# USB_UART.net
KiCad netlist of a schematic drawn in Altium Designer
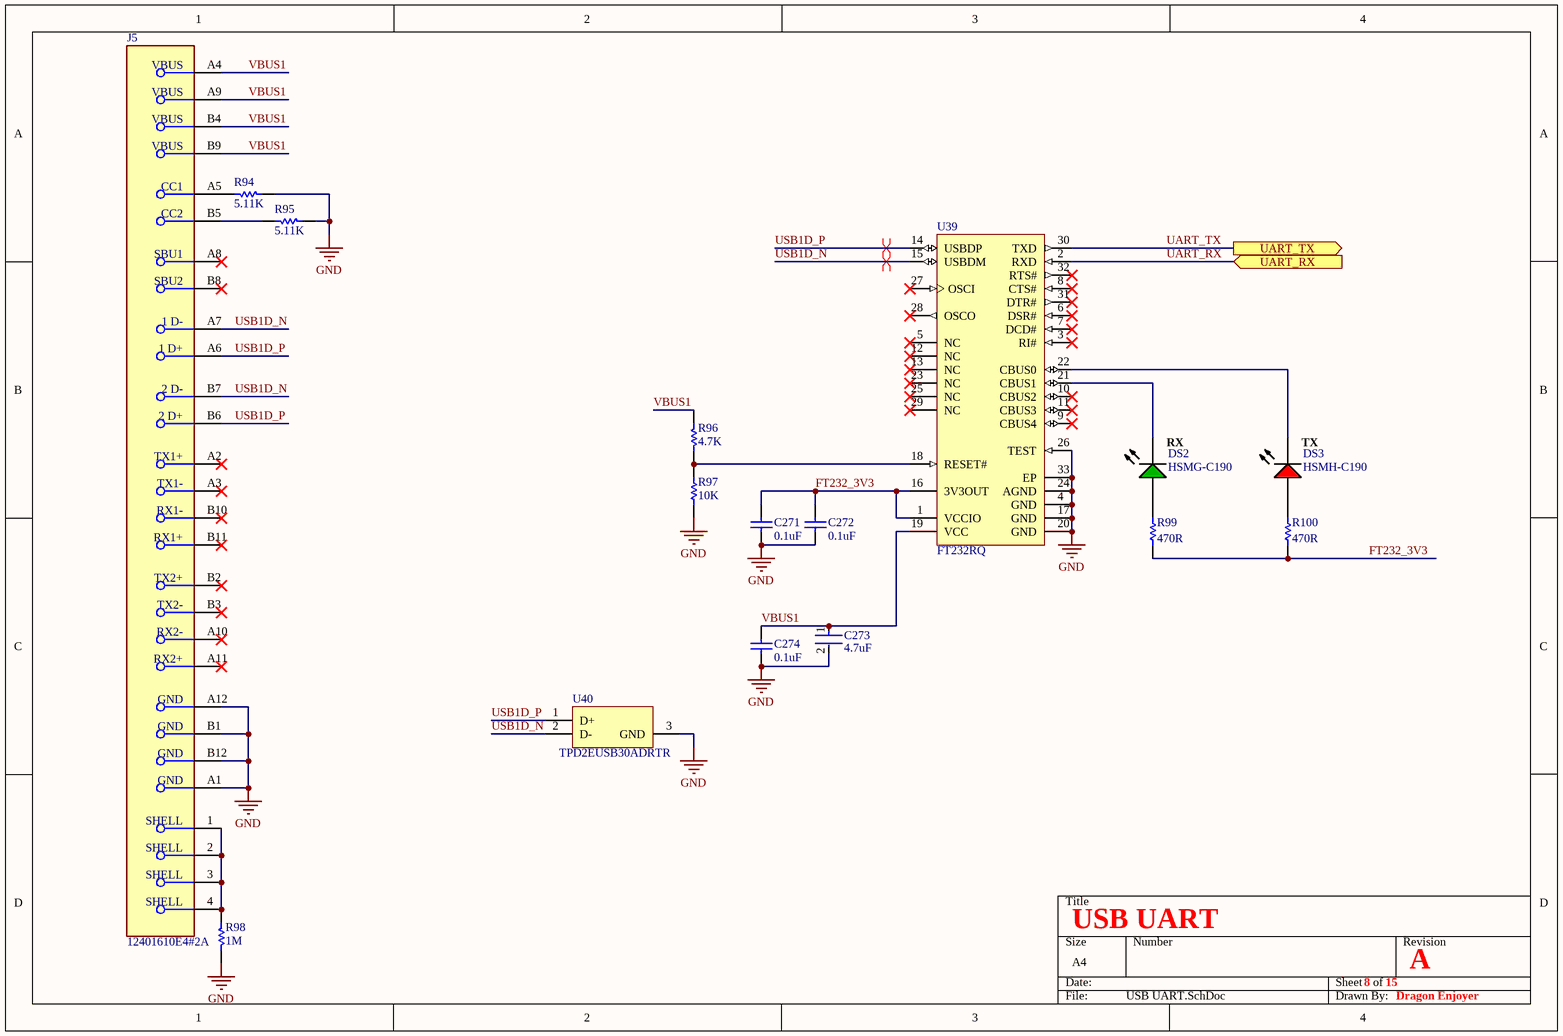
[diagram p0: USB UART.SchDoc]

(export (version "E")
  (design (tool "Eeschema 10.0.6"))
  (components
    (comp (ref "C271")
      (value "0.1uF")
      (footprint "CAPC1005X56X25LL10T15")
      (fields
        (field (name "MANUFACTURER") "AVX Interconnect / Elco")
        (field (name "PART NUMBER") "04026D104KAT2A")
      )
      (libsource (lib "Altium Content Vault") (part "CAP"))
    )
    (comp (ref "C272")
      (value "0.1uF")
      (footprint "CAPC1005X56X25LL10T15")
      (fields
        (field (name "MANUFACTURER") "AVX Interconnect / Elco")
        (field (name "PART NUMBER") "04026D104KAT2A")
      )
      (libsource (lib "Altium Content Vault") (part "CAP"))
    )
    (comp (ref "C273")
      (value "C1005X5R1A475K050BC")
      (footprint "FP-C1005-050-0_15-MFG")
      (description "CAP CER 4.7UF 10V X5R 0402")
      (fields (field (name "TOLERANCE") "10%") (field (name "CAPACITANCE") "4.7uF"))
      (libsource (lib "Altium Content Vault") (part "b4654b650e69147ec39a6b967a45e02"))
    )
    (comp (ref "C274")
      (value "0.1uF")
      (footprint "CAPC1005X56X25LL10T15")
      (fields
        (field (name "MANUFACTURER") "AVX Interconnect / Elco")
        (field (name "PART NUMBER") "04026D104KAT2A")
      )
      (libsource (lib "Altium Content Vault") (part "CAP"))
    )
    (comp (ref "DS2")
      (value "HSMG-C190")
      (footprint "AVAG-HSMX-C190_V")
      (description "Chip LED, Green, 2.2 V, -40 to 85 degC, 2-Pin SMD, RoHS, Tape and Reel")
      (libsource (lib "Altium Content Vault") (part "LED-GREEN-AK-2"))
    )
    (comp (ref "DS3")
      (value "HSMH-C190")
      (footprint "AVAG-HSMX-C190_V")
      (description "LED Uni-Color Red, 65 mW, 20 mA, -40 to 85 degC, 2-Pin SMD, RoHS, Tape and Reel")
      (libsource (lib "Altium Content Vault") (part "LED-RED-AK-2"))
    )
    (comp (ref "J5")
      (value "12401610E4#2A")
      (footprint "FP-12401610E4#2A-MFG")
      (description "CONN RCP USB3.1 TYPEC 24P SMD RA")
      (libsource (lib "Altium Content Vault") (part "7c76f4c47d7e2af8b8797da79635f2a"))
    )
    (comp (ref "R94")
      (value "5.11K")
      (footprint "RESC0603X28X15ML05T05")
      (fields (field (name "PART NUMBER") "CRCW02015K11FNED") (field (name "MANUFACTURER") "Vishay Dale"))
      (libsource (lib "Altium Content Vault") (part "RES"))
    )
    (comp (ref "R95")
      (value "5.11K")
      (footprint "RESC0603X28X15ML05T05")
      (fields (field (name "PART NUMBER") "CRCW02015K11FNED") (field (name "MANUFACTURER") "Vishay Dale"))
      (libsource (lib "Altium Content Vault") (part "RES"))
    )
    (comp (ref "R96")
      (value "4.7K")
      (footprint "RESC1005X40X25LL05T10")
      (fields (field (name "PART NUMBER") "RC0402JR-074K7L") (field (name "MANUFACTURER") "Yageo / Phycomp"))
      (libsource (lib "Altium Content Vault") (part "RES"))
    )
    (comp (ref "R97")
      (value "10K")
      (footprint "RESC1005X40X25LL05T10")
      (fields (field (name "PART NUMBER") "RC0402FR-0710KL") (field (name "MANUFACTURER") "Yageo / Phycomp"))
      (libsource (lib "Altium Content Vault") (part "RES"))
    )
    (comp (ref "R98")
      (value "1M")
      (footprint "RESC1005X40X25ML05T05")
      (fields (field (name "MANUFACTURER") "Panasonic") (field (name "PART NUMBER") "ERJ-2GEJ105X"))
      (libsource (lib "Altium Content Vault") (part "RES"))
    )
    (comp (ref "R99")
      (value "470R")
      (footprint "RESC0603X26X15LL03T05")
      (fields (field (name "MANUFACTURER") "Panasonic") (field (name "PART NUMBER") "ERJ1GNF4700C"))
      (libsource (lib "Altium Content Vault") (part "RES"))
    )
    (comp (ref "R100")
      (value "470R")
      (footprint "RESC0603X26X15LL03T05")
      (fields (field (name "MANUFACTURER") "Panasonic") (field (name "PART NUMBER") "ERJ1GNF4700C"))
      (libsource (lib "Altium Content Vault") (part "RES"))
    )
    (comp (ref "U39")
      (value "FT232RQ")
      (footprint "FTDI-QFN-32_3200X3200EP_V")
      (description "USB-to-UART 1-CH 256byte FIFO 5V 32-Pin QFN EP Tray")
      (fields (field (name "MANUFACTURER") "FTDI"))
      (libsource (lib "Altium Content Vault") (part "FTDI-FT232-QFN-32"))
    )
    (comp (ref "U40")
      (value "TPD2EUSB30ADRTR")
      (footprint "DRT0003A")
      (fields (field (name "MANUFACTURER") "Texas Instruments"))
      (libsource (lib "Altium Content Vault") (part "TI-TPD2EUSB30A-SOT_DRT-3"))
    )
  )
  (nets
    (net (code "1") (name "/FT232_3V3") (class "Default")
      (node (ref "C271") (pin "2") (pinfunction "2_2") (pintype "passive"))
      (node (ref "C272") (pin "2") (pinfunction "2_2") (pintype "passive"))
      (node (ref "R100") (pin "1") (pinfunction "1_1") (pintype "passive"))
      (node (ref "R99") (pin "1") (pinfunction "1_1") (pintype "passive"))
      (node (ref "U39") (pin "1") (pinfunction "VCCIO_1") (pintype "power_in"))
      (node (ref "U39") (pin "16") (pinfunction "3V3OUT_16") (pintype "power_in"))
    )
    (net (code "2") (name "/UART_RX") (class "Default")
      (node (ref "U39") (pin "2") (pinfunction "RXD_2") (pintype "input"))
    )
    (net (code "3") (name "/UART_TX") (class "Default")
      (node (ref "U39") (pin "30") (pinfunction "TXD_30") (pintype "output"))
    )
    (net (code "4") (name "/USB1D_N") (class "Default")
      (node (ref "J5") (pin "A7") (pinfunction "1_D-_A7") (pintype "passive"))
      (node (ref "J5") (pin "B7") (pinfunction "2_D-_B7") (pintype "passive"))
      (node (ref "U39") (pin "15") (pinfunction "USBDM_15") (pintype "bidirectional"))
      (node (ref "U40") (pin "2") (pinfunction "D-_2") (pintype "passive"))
    )
    (net (code "5") (name "/USB1D_P") (class "Default")
      (node (ref "J5") (pin "A6") (pinfunction "1_D+_A6") (pintype "passive"))
      (node (ref "J5") (pin "B6") (pinfunction "2_D+_B6") (pintype "passive"))
      (node (ref "U39") (pin "14") (pinfunction "USBDP_14") (pintype "bidirectional"))
      (node (ref "U40") (pin "1") (pinfunction "D+_1") (pintype "passive"))
    )
    (net (code "6") (name "/VBUS1") (class "Default")
      (node (ref "C273") (pin "1") (pinfunction "1_1") (pintype "passive"))
      (node (ref "C274") (pin "2") (pinfunction "2_2") (pintype "passive"))
      (node (ref "J5") (pin "A4") (pinfunction "VBUS_A4") (pintype "passive"))
      (node (ref "J5") (pin "A9") (pinfunction "VBUS_A9") (pintype "passive"))
      (node (ref "J5") (pin "B4") (pinfunction "VBUS_B4") (pintype "passive"))
      (node (ref "J5") (pin "B9") (pinfunction "VBUS_B9") (pintype "passive"))
      (node (ref "R96") (pin "2") (pinfunction "2_2") (pintype "passive"))
      (node (ref "U39") (pin "19") (pinfunction "VCC_19") (pintype "power_in"))
    )
    (net (code "7") (name "GND") (class "Default")
      (node (ref "C271") (pin "1") (pinfunction "1_1") (pintype "passive"))
      (node (ref "C272") (pin "1") (pinfunction "1_1") (pintype "passive"))
      (node (ref "C273") (pin "2") (pinfunction "2_2") (pintype "passive"))
      (node (ref "C274") (pin "1") (pinfunction "1_1") (pintype "passive"))
      (node (ref "J5") (pin "A1") (pinfunction "GND_A1") (pintype "power_in"))
      (node (ref "J5") (pin "A12") (pinfunction "GND_A12") (pintype "power_in"))
      (node (ref "J5") (pin "B1") (pinfunction "GND_B1") (pintype "power_in"))
      (node (ref "J5") (pin "B12") (pinfunction "GND_B12") (pintype "power_in"))
      (node (ref "R94") (pin "1") (pinfunction "1_1") (pintype "passive"))
      (node (ref "R95") (pin "1") (pinfunction "1_1") (pintype "passive"))
      (node (ref "R97") (pin "1") (pinfunction "1_1") (pintype "passive"))
      (node (ref "R98") (pin "1") (pinfunction "1_1") (pintype "passive"))
      (node (ref "U39") (pin "17") (pinfunction "GND_17") (pintype "passive"))
      (node (ref "U39") (pin "20") (pinfunction "GND_20") (pintype "passive"))
      (node (ref "U39") (pin "24") (pinfunction "AGND_24") (pintype "passive"))
      (node (ref "U39") (pin "26") (pinfunction "TEST_26") (pintype "input"))
      (node (ref "U39") (pin "33") (pinfunction "EP_33") (pintype "passive"))
      (node (ref "U39") (pin "4") (pinfunction "GND_4") (pintype "passive"))
      (node (ref "U40") (pin "3") (pinfunction "GND_3") (pintype "passive"))
    )
    (net (code "8") (name "Net-(DS2-A)") (class "Default")
      (node (ref "DS2") (pin "1") (pinfunction "A_1") (pintype "passive"))
      (node (ref "R99") (pin "2") (pinfunction "2_2") (pintype "passive"))
    )
    (net (code "9") (name "Net-(DS2-K)") (class "Default")
      (node (ref "DS2") (pin "2") (pinfunction "K_2") (pintype "passive"))
      (node (ref "U39") (pin "21") (pinfunction "CBUS1_21") (pintype "bidirectional"))
    )
    (net (code "10") (name "Net-(DS3-A)") (class "Default")
      (node (ref "DS3") (pin "1") (pinfunction "A_1") (pintype "passive"))
      (node (ref "R100") (pin "2") (pinfunction "2_2") (pintype "passive"))
    )
    (net (code "11") (name "Net-(DS3-K)") (class "Default")
      (node (ref "DS3") (pin "2") (pinfunction "K_2") (pintype "passive"))
      (node (ref "U39") (pin "22") (pinfunction "CBUS0_22") (pintype "bidirectional"))
    )
    (net (code "12") (name "Net-(J5-CC1)") (class "Default")
      (node (ref "J5") (pin "A5") (pinfunction "CC1_A5") (pintype "passive"))
      (node (ref "R94") (pin "2") (pinfunction "2_2") (pintype "passive"))
    )
    (net (code "13") (name "Net-(J5-CC2)") (class "Default")
      (node (ref "J5") (pin "B5") (pinfunction "CC2_B5") (pintype "passive"))
      (node (ref "R95") (pin "2") (pinfunction "2_2") (pintype "passive"))
    )
    (net (code "14") (name "Net-(J5-SHELL-Pad1)") (class "Default")
      (node (ref "J5") (pin "1") (pinfunction "SHELL_1") (pintype "power_in"))
      (node (ref "J5") (pin "2") (pinfunction "SHELL_2") (pintype "power_in"))
      (node (ref "J5") (pin "3") (pinfunction "SHELL_3") (pintype "power_in"))
      (node (ref "J5") (pin "4") (pinfunction "SHELL_4") (pintype "power_in"))
      (node (ref "R98") (pin "2") (pinfunction "2_2") (pintype "passive"))
    )
    (net (code "15") (name "Net-(U39-RESET#)") (class "Default")
      (node (ref "R96") (pin "1") (pinfunction "1_1") (pintype "passive"))
      (node (ref "R97") (pin "2") (pinfunction "2_2") (pintype "passive"))
      (node (ref "U39") (pin "18") (pinfunction "RESET#_18") (pintype "input"))
    )
    (net (code "16") (name "unconnected-(J5-RX1+-PadB11)") (class "Default")
      (node (ref "J5") (pin "B11") (pinfunction "RX1+_B11") (pintype "passive+no_connect"))
    )
    (net (code "17") (name "unconnected-(J5-RX1--PadB10)") (class "Default")
      (node (ref "J5") (pin "B10") (pinfunction "RX1-_B10") (pintype "passive+no_connect"))
    )
    (net (code "18") (name "unconnected-(J5-RX2+-PadA11)") (class "Default")
      (node (ref "J5") (pin "A11") (pinfunction "RX2+_A11") (pintype "passive+no_connect"))
    )
    (net (code "19") (name "unconnected-(J5-RX2--PadA10)") (class "Default")
      (node (ref "J5") (pin "A10") (pinfunction "RX2-_A10") (pintype "passive+no_connect"))
    )
    (net (code "20") (name "unconnected-(J5-SBU1-PadA8)") (class "Default")
      (node (ref "J5") (pin "A8") (pinfunction "SBU1_A8") (pintype "passive+no_connect"))
    )
    (net (code "21") (name "unconnected-(J5-SBU2-PadB8)") (class "Default")
      (node (ref "J5") (pin "B8") (pinfunction "SBU2_B8") (pintype "passive+no_connect"))
    )
    (net (code "22") (name "unconnected-(J5-TX1+-PadA2)") (class "Default")
      (node (ref "J5") (pin "A2") (pinfunction "TX1+_A2") (pintype "passive+no_connect"))
    )
    (net (code "23") (name "unconnected-(J5-TX1--PadA3)") (class "Default")
      (node (ref "J5") (pin "A3") (pinfunction "TX1-_A3") (pintype "passive+no_connect"))
    )
    (net (code "24") (name "unconnected-(J5-TX2+-PadB2)") (class "Default")
      (node (ref "J5") (pin "B2") (pinfunction "TX2+_B2") (pintype "passive+no_connect"))
    )
    (net (code "25") (name "unconnected-(J5-TX2--PadB3)") (class "Default")
      (node (ref "J5") (pin "B3") (pinfunction "TX2-_B3") (pintype "passive+no_connect"))
    )
    (net (code "26") (name "unconnected-(U39-CBUS2-Pad10)") (class "Default")
      (node (ref "U39") (pin "10") (pinfunction "CBUS2_10") (pintype "bidirectional+no_connect"))
    )
    (net (code "27") (name "unconnected-(U39-CBUS3-Pad11)") (class "Default")
      (node (ref "U39") (pin "11") (pinfunction "CBUS3_11") (pintype "bidirectional+no_connect"))
    )
    (net (code "28") (name "unconnected-(U39-CBUS4-Pad9)") (class "Default")
      (node (ref "U39") (pin "9") (pinfunction "CBUS4_9") (pintype "bidirectional+no_connect"))
    )
    (net (code "29") (name "unconnected-(U39-CTS#-Pad8)") (class "Default")
      (node (ref "U39") (pin "8") (pinfunction "CTS#_8") (pintype "input+no_connect"))
    )
    (net (code "30") (name "unconnected-(U39-DCD#-Pad7)") (class "Default")
      (node (ref "U39") (pin "7") (pinfunction "DCD#_7") (pintype "input+no_connect"))
    )
    (net (code "31") (name "unconnected-(U39-DSR#-Pad6)") (class "Default")
      (node (ref "U39") (pin "6") (pinfunction "DSR#_6") (pintype "input+no_connect"))
    )
    (net (code "32") (name "unconnected-(U39-DTR#-Pad31)") (class "Default")
      (node (ref "U39") (pin "31") (pinfunction "DTR#_31") (pintype "output+no_connect"))
    )
    (net (code "33") (name "unconnected-(U39-NC-Pad5)") (class "Default")
      (node (ref "U39") (pin "5") (pinfunction "NC_5") (pintype "passive+no_connect"))
    )
    (net (code "34") (name "unconnected-(U39-NC-Pad12)") (class "Default")
      (node (ref "U39") (pin "12") (pinfunction "NC_12") (pintype "passive+no_connect"))
    )
    (net (code "35") (name "unconnected-(U39-NC-Pad13)") (class "Default")
      (node (ref "U39") (pin "13") (pinfunction "NC_13") (pintype "passive+no_connect"))
    )
    (net (code "36") (name "unconnected-(U39-NC-Pad23)") (class "Default")
      (node (ref "U39") (pin "23") (pinfunction "NC_23") (pintype "passive+no_connect"))
    )
    (net (code "37") (name "unconnected-(U39-NC-Pad25)") (class "Default")
      (node (ref "U39") (pin "25") (pinfunction "NC_25") (pintype "passive+no_connect"))
    )
    (net (code "38") (name "unconnected-(U39-NC-Pad29)") (class "Default")
      (node (ref "U39") (pin "29") (pinfunction "NC_29") (pintype "passive+no_connect"))
    )
    (net (code "39") (name "unconnected-(U39-OSCI-Pad27)") (class "Default")
      (node (ref "U39") (pin "27") (pinfunction "OSCI_27") (pintype "input+no_connect"))
    )
    (net (code "40") (name "unconnected-(U39-OSCO-Pad28)") (class "Default")
      (node (ref "U39") (pin "28") (pinfunction "OSCO_28") (pintype "output+no_connect"))
    )
    (net (code "41") (name "unconnected-(U39-RI#-Pad3)") (class "Default")
      (node (ref "U39") (pin "3") (pinfunction "RI#_3") (pintype "input+no_connect"))
    )
    (net (code "42") (name "unconnected-(U39-RTS#-Pad32)") (class "Default")
      (node (ref "U39") (pin "32") (pinfunction "RTS#_32") (pintype "output+no_connect"))
    )
  )
)
